# lem_current_sensor.net
KiCad netlist of a schematic drawn in EAGLE
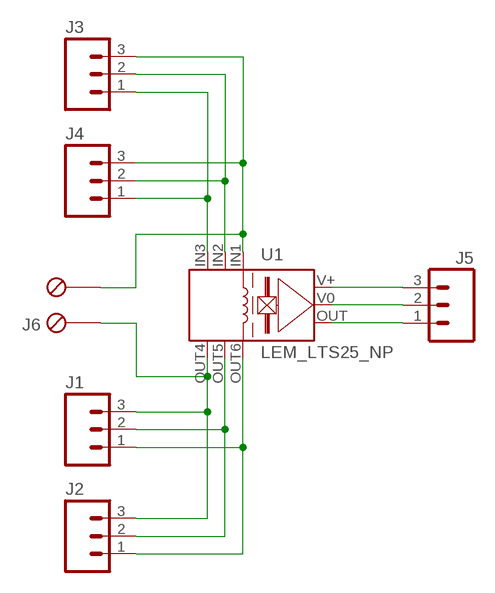
[diagram p0: schematic, sheet 1]

(export (version "E")
  (design (tool "Eeschema 10.0.6"))
  (components
    (comp (ref "J1")
      (value "M03LONGPADS")
      (footprint "eagle-import:1X03_LONGPADS")
      (libsource (lib "eagle-import") (part "M03LONGPADS"))
    )
    (comp (ref "J2")
      (value "M03LONGPADS")
      (footprint "eagle-import:1X03_LONGPADS")
      (libsource (lib "eagle-import") (part "M03LONGPADS"))
    )
    (comp (ref "J3")
      (value "M03LONGPADS")
      (footprint "eagle-import:1X03_LONGPADS")
      (libsource (lib "eagle-import") (part "M03LONGPADS"))
    )
    (comp (ref "J4")
      (value "M03LONGPADS")
      (footprint "eagle-import:1X03_LONGPADS")
      (libsource (lib "eagle-import") (part "M03LONGPADS"))
    )
    (comp (ref "J5")
      (value "M03LONGPADS")
      (footprint "eagle-import:1X03_LONGPADS")
      (libsource (lib "eagle-import") (part "M03LONGPADS"))
    )
    (comp (ref "J6")
      (value "METALTEX-2")
      (footprint "eagle-import:METALTEX-2")
      (libsource (lib "eagle-import") (part "METALTEX-2"))
    )
    (comp (ref "U1")
      (value "LEM_LTS25_NP")
      (footprint "eagle-import:LTS25_NP")
      (libsource (lib "eagle-import") (part "LEM_LTS25_NP"))
    )
  )
  (nets
    (net (code "1") (name "Net-(J1-Pad1)") (class "Default")
      (node (ref "J1") (pin "1") (pinfunction "1_1") (pintype "passive"))
      (node (ref "J2") (pin "1") (pinfunction "1_1") (pintype "passive"))
      (node (ref "U1") (pin "OUT6") (pinfunction "OUT6_OUT6") (pintype "output"))
    )
    (net (code "2") (name "Net-(J1-Pad2)") (class "Default")
      (node (ref "J1") (pin "2") (pinfunction "2_2") (pintype "passive"))
      (node (ref "J2") (pin "2") (pinfunction "2_2") (pintype "passive"))
      (node (ref "U1") (pin "OUT5") (pinfunction "OUT5_OUT5") (pintype "output"))
    )
    (net (code "3") (name "Net-(J1-Pad3)") (class "Default")
      (node (ref "J1") (pin "3") (pinfunction "3_3") (pintype "passive"))
      (node (ref "J2") (pin "3") (pinfunction "3_3") (pintype "passive"))
      (node (ref "J6") (pin "P1") (pinfunction "P1_P1") (pintype "bidirectional"))
      (node (ref "U1") (pin "OUT4") (pinfunction "OUT4_OUT4") (pintype "output"))
    )
    (net (code "4") (name "Net-(J3-Pad1)") (class "Default")
      (node (ref "J3") (pin "1") (pinfunction "1_1") (pintype "passive"))
      (node (ref "J4") (pin "1") (pinfunction "1_1") (pintype "passive"))
      (node (ref "U1") (pin "IN3") (pinfunction "IN3_IN3") (pintype "input"))
    )
    (net (code "5") (name "Net-(J3-Pad2)") (class "Default")
      (node (ref "J3") (pin "2") (pinfunction "2_2") (pintype "passive"))
      (node (ref "J4") (pin "2") (pinfunction "2_2") (pintype "passive"))
      (node (ref "U1") (pin "IN2") (pinfunction "IN2_IN2") (pintype "input"))
    )
    (net (code "6") (name "Net-(J3-Pad3)") (class "Default")
      (node (ref "J3") (pin "3") (pinfunction "3_3") (pintype "passive"))
      (node (ref "J4") (pin "3") (pinfunction "3_3") (pintype "passive"))
      (node (ref "J6") (pin "P2") (pinfunction "P2_P2") (pintype "bidirectional"))
      (node (ref "U1") (pin "IN1") (pinfunction "IN1_IN1") (pintype "input"))
    )
    (net (code "7") (name "Net-(J5-Pad3)") (class "Default")
      (node (ref "J5") (pin "3") (pinfunction "3_3") (pintype "passive"))
      (node (ref "U1") (pin "V+") (pinfunction "V+_V+") (pintype "input"))
    )
    (net (code "8") (name "Net-(U1-0V)") (class "Default")
      (node (ref "J5") (pin "2") (pinfunction "2_2") (pintype "passive"))
      (node (ref "U1") (pin "V0") (pinfunction "0V_V0") (pintype "input"))
    )
    (net (code "9") (name "Net-(U1-VOUT)") (class "Default")
      (node (ref "J5") (pin "1") (pinfunction "1_1") (pintype "passive"))
      (node (ref "U1") (pin "OUT") (pinfunction "VOUT_OUT") (pintype "output"))
    )
  )
)
